# MSE312_SIMRACER.net
KiCad netlist of a schematic drawn in Altium Designer
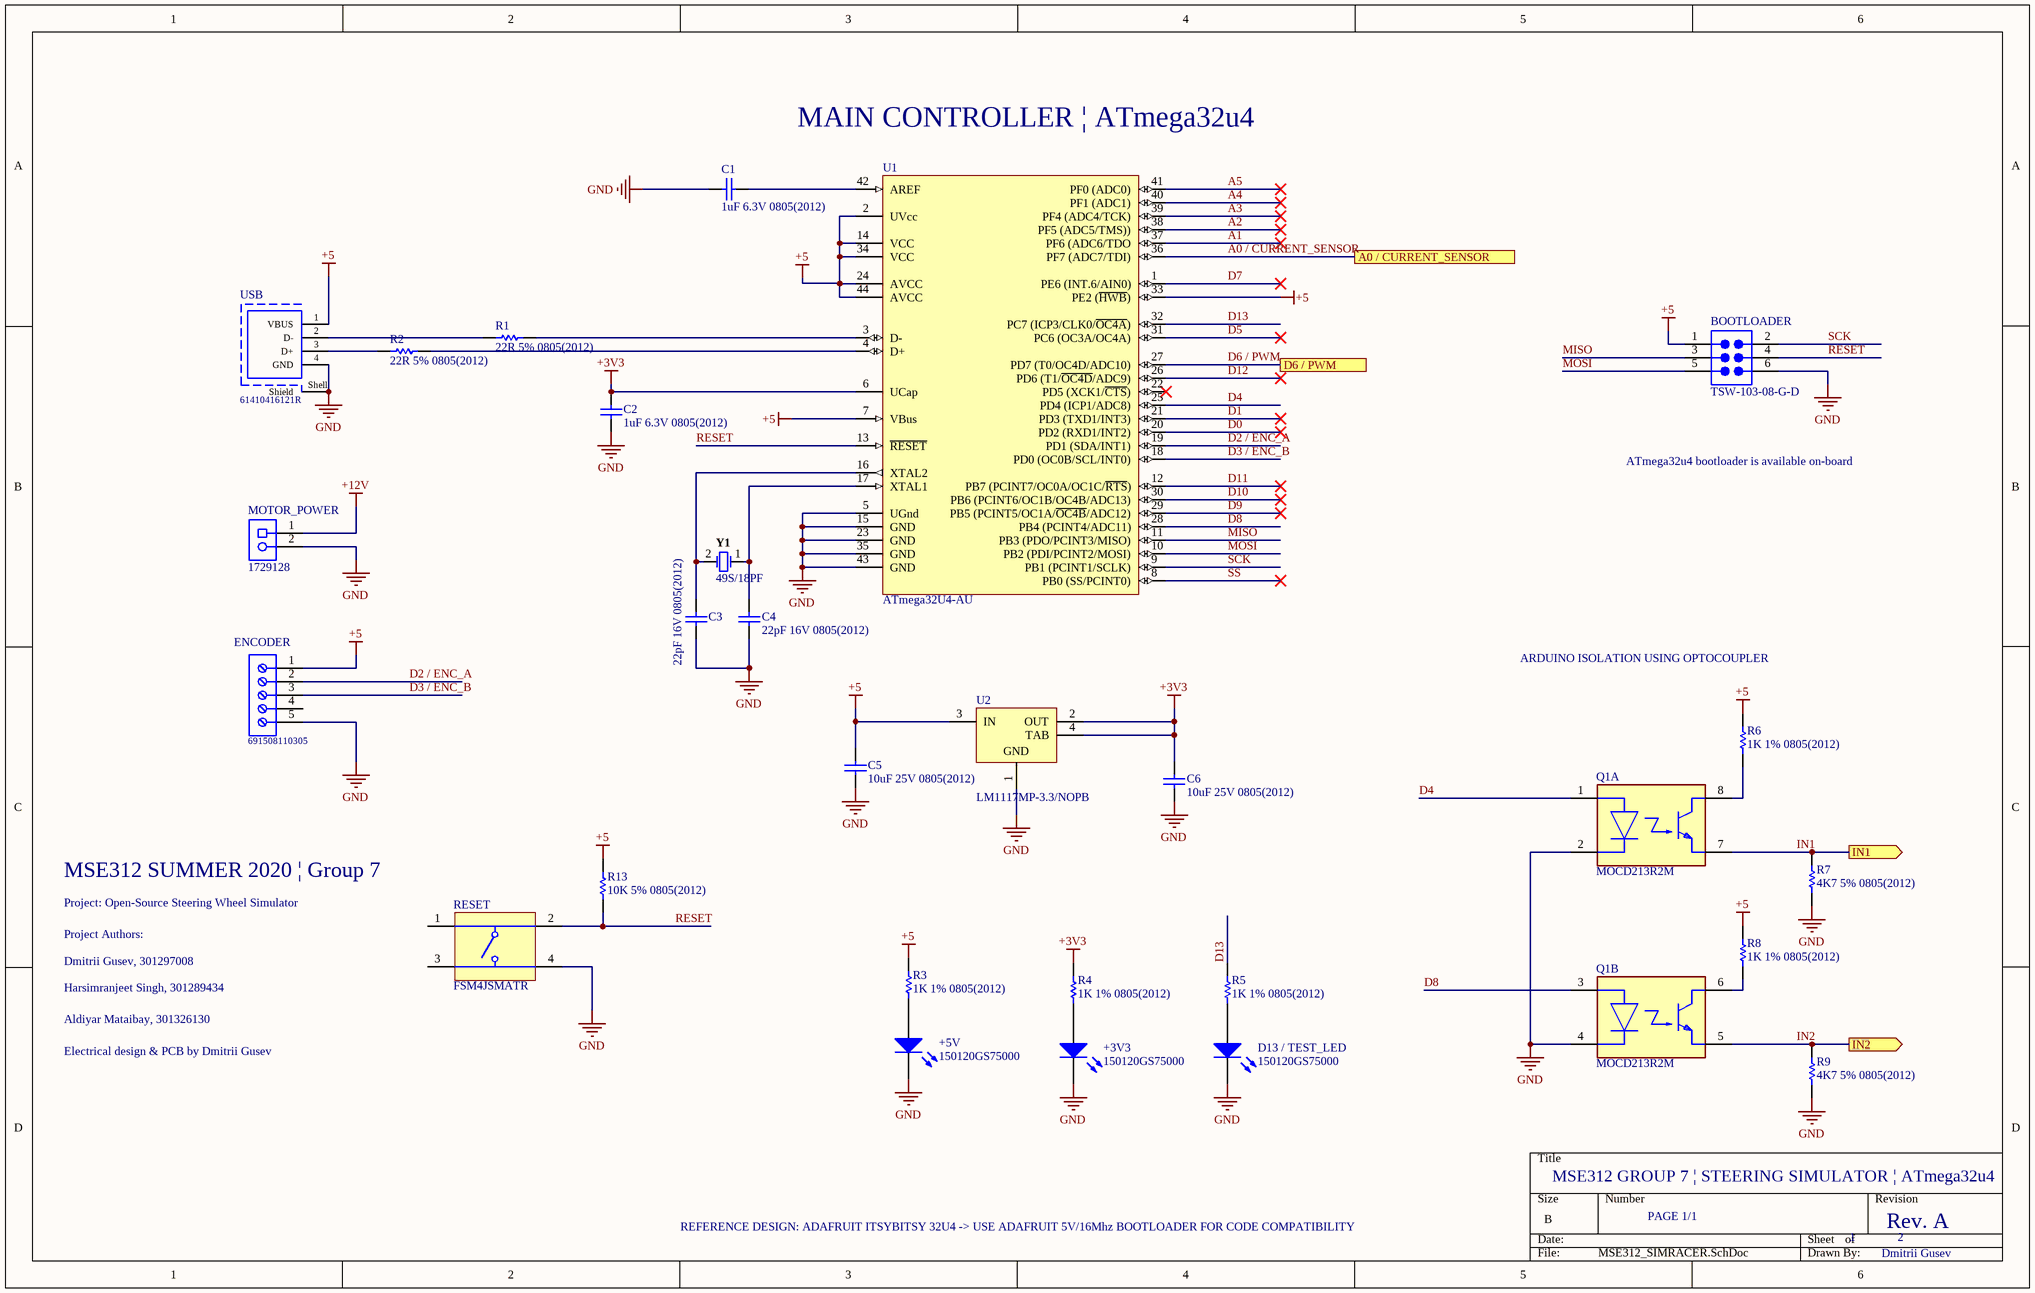
[diagram p0: MSE312_SIMRACER.SchDoc]

(export (version "E")
  (design (tool "Eeschema 10.0.6"))
  (components
    (comp (ref "+3V3")
      (value "150120GS75000")
      (footprint "1206_A")
      (description "SMD mono-color Chip LED, WL-SMCW, Green")
      (fields (field (name "MANUFACTURER") "Wuerth Elektronik"))
      (libsource (lib "Altium Content Vault") (part "WE-LED_K1A2-2"))
    )
    (comp (ref "+5V")
      (value "150120GS75000")
      (footprint "1206_A")
      (description "SMD mono-color Chip LED, WL-SMCW, Green")
      (fields (field (name "MANUFACTURER") "Wuerth Elektronik"))
      (libsource (lib "Altium Content Vault") (part "WE-LED_K1A2-2"))
    )
    (comp (ref "BOOTLOADER")
      (value "TSW-103-08-G-D")
      (footprint "SMTC-TSW-103-08-X-D")
      (fields (field (name "MANUFACTURER") "Samtec"))
      (libsource (lib "Altium Content Vault") (part "SMTC-TSW-103-08-X-D"))
    )
    (comp (ref "C1")
      (value "1uF 6.3V 0805(2012)")
      (footprint "CAPC0805(2012)145_N")
      (description "CAP 1uF 6.3V ±10% 0805 (2012 Metric) Thickness 1.45mm SMD")
      (fields (field (name "TOLERANCE") "Â±10%"))
      (libsource (lib "Altium Content Vault") (part "CAP"))
    )
    (comp (ref "C2")
      (value "1uF 6.3V 0805(2012)")
      (footprint "CAPC0805(2012)145_N")
      (description "CAP 1uF 6.3V ±10% 0805 (2012 Metric) Thickness 1.45mm SMD")
      (fields (field (name "TOLERANCE") "Â±10%"))
      (libsource (lib "Altium Content Vault") (part "CAP"))
    )
    (comp (ref "C3")
      (value "22pF 16V 0805(2012)")
      (footprint "CAPC0805(2012)100_N")
      (description "CAP 22pF 16V ±0.5pF 0805 (2012 Metric) Thickness 1mm SMD")
      (fields (field (name "TOLERANCE") "Â±0.5pF"))
      (libsource (lib "Altium Content Vault") (part "CAP"))
    )
    (comp (ref "C4")
      (value "22pF 16V 0805(2012)")
      (footprint "CAPC0805(2012)100_N")
      (description "CAP 22pF 16V ±0.5pF 0805 (2012 Metric) Thickness 1mm SMD")
      (fields (field (name "TOLERANCE") "Â±0.5pF"))
      (libsource (lib "Altium Content Vault") (part "CAP"))
    )
    (comp (ref "C5")
      (value "10uF 25V 0805(2012)")
      (footprint "CAPC0805(2012)145_N")
      (description "CAP 10uF 25V ±10% 0805 (2012 Metric) Thickness 1.45mm SMD")
      (fields (field (name "TOLERANCE") "Â±10%"))
      (libsource (lib "Altium Content Vault") (part "CAP"))
    )
    (comp (ref "C6")
      (value "10uF 25V 0805(2012)")
      (footprint "CAPC0805(2012)145_N")
      (description "CAP 10uF 25V ±10% 0805 (2012 Metric) Thickness 1.45mm SMD")
      (fields (field (name "TOLERANCE") "Â±10%"))
      (libsource (lib "Altium Content Vault") (part "CAP"))
    )
    (comp (ref "D13 / TEST_LED")
      (value "150120GS75000")
      (footprint "1206_A")
      (description "SMD mono-color Chip LED, WL-SMCW, Green")
      (fields (field (name "MANUFACTURER") "Wuerth Elektronik"))
      (libsource (lib "Altium Content Vault") (part "WE-LED_K1A2-2"))
    )
    (comp (ref "ENCODER")
      (value "691508110305")
      (footprint "691508110305")
      (description "Serie 5081 - 3.50 mm Horizontal Entry SMT with Rising Cage Clamp WR-TBL, 5 pin")
      (fields (field (name "MANUFACTURER") "Wurth Elektronik") (field (name "PUBLISHER") "WurthElektronik"))
      (libsource (lib "Altium Content Vault") (part "WE-CN-1P-F-TB5"))
    )
    (comp (ref "MOTOR_POWER")
      (value "1729128")
      (footprint "PHOE-1729128-2_V")
      (description "PCB Terminal Block, 13.5 A, 400 V, 2-Pin THD, RoHS, Bulk")
      (fields (field (name "MANUFACTURER") "Phoenix Contact"))
      (libsource (lib "Altium Content Vault") (part "CN-2P-F-R2"))
    )
    (comp (ref "Q1")
      (value "MOCD213R2M")
      (footprint "FP-751DZ-MFG")
      (description "OPTOISO 2.5KV 2CH TRANS 8SOIC")
      (fields
        (field (name "MANUFACTURER") "ON Semiconductor")
        (field (name "OCTOPART") "https://octopart.com/mocd213r2m-on+semiconductor-84330505")
      )
      (libsource (lib "Altium Content Vault") (part "5ad21a7a4ea51725ba3cd103b04639f"))
    )
    (comp (ref "R1")
      (value "22R 5% 0805(2012)")
      (footprint "RESC0805(2012)_M")
      (description "22R 0.125W 5% 0805 (2012 Metric)  SMD")
      (fields (field (name "POWER") "0.125 W") (field (name "TOLERANCE") "5 %"))
      (libsource (lib "Altium Content Vault") (part "RES"))
    )
    (comp (ref "R2")
      (value "22R 5% 0805(2012)")
      (footprint "RESC0805(2012)_M")
      (description "22R 0.125W 5% 0805 (2012 Metric)  SMD")
      (fields (field (name "POWER") "0.125 W") (field (name "TOLERANCE") "5 %"))
      (libsource (lib "Altium Content Vault") (part "RES"))
    )
    (comp (ref "R3")
      (value "1K 1% 0805(2012)")
      (footprint "RESC0805(2012)_M")
      (description "1K 0.125W 1% 0805 (2012 Metric)  SMD")
      (fields (field (name "TOLERANCE") "1 %") (field (name "POWER") "0.125 W"))
      (libsource (lib "Altium Content Vault") (part "RES"))
    )
    (comp (ref "R4")
      (value "1K 1% 0805(2012)")
      (footprint "RESC0805(2012)_M")
      (description "1K 0.125W 1% 0805 (2012 Metric)  SMD")
      (fields (field (name "TOLERANCE") "1 %") (field (name "POWER") "0.125 W"))
      (libsource (lib "Altium Content Vault") (part "RES"))
    )
    (comp (ref "R5")
      (value "1K 1% 0805(2012)")
      (footprint "RESC0805(2012)_M")
      (description "1K 0.125W 1% 0805 (2012 Metric)  SMD")
      (fields (field (name "TOLERANCE") "1 %") (field (name "POWER") "0.125 W"))
      (libsource (lib "Altium Content Vault") (part "RES"))
    )
    (comp (ref "R6")
      (value "1K 1% 0805(2012)")
      (footprint "RESC0805(2012)_M")
      (description "1K 0.125W 1% 0805 (2012 Metric)  SMD")
      (fields (field (name "TOLERANCE") "1 %") (field (name "POWER") "0.125 W"))
      (libsource (lib "Altium Content Vault") (part "RES"))
    )
    (comp (ref "R7")
      (value "4K7 5% 0805(2012)")
      (footprint "RESC0805(2012)_N")
      (description "4K7 0.125W 5% 0805 (2012 Metric)  SMD")
      (fields (field (name "POWER") "0.125 W") (field (name "TOLERANCE") "5 %"))
      (libsource (lib "Altium Content Vault") (part "RES"))
    )
    (comp (ref "R8")
      (value "1K 1% 0805(2012)")
      (footprint "RESC0805(2012)_M")
      (description "1K 0.125W 1% 0805 (2012 Metric)  SMD")
      (fields (field (name "TOLERANCE") "1 %") (field (name "POWER") "0.125 W"))
      (libsource (lib "Altium Content Vault") (part "RES"))
    )
    (comp (ref "R9")
      (value "4K7 5% 0805(2012)")
      (footprint "RESC0805(2012)_N")
      (description "4K7 0.125W 5% 0805 (2012 Metric)  SMD")
      (fields (field (name "POWER") "0.125 W") (field (name "TOLERANCE") "5 %"))
      (libsource (lib "Altium Content Vault") (part "RES"))
    )
    (comp (ref "R13")
      (value "10K 5% 0805(2012)")
      (footprint "RESC0805(2012)_L")
      (description "10K 0.125W 5% 0805 (2012 Metric)  SMD")
      (fields (field (name "POWER") "0.125 W") (field (name "TOLERANCE") "5 %"))
      (libsource (lib "Altium Content Vault") (part "RES"))
    )
    (comp (ref "RESET")
      (value "FSM4JSMATR")
      (footprint "TECO-FSM4JSMATR_V")
      (description "Micro Miniature Push Button Switch FSM JSM, 50 mA, -35 to 85 degC, 4-Pin SMD, RoHS, Tape and Reel")
      (fields (field (name "MANUFACTURER") "TE Connectivity"))
      (libsource (lib "Altium Content Vault") (part "SW-SPST-4_A"))
    )
    (comp (ref "U1")
      (value "ATmega32U4-AU")
      (footprint "44ML_M")
      (libsource (lib "Altium Content Vault") (part "MC-8B-ATM16U4-SQ44"))
    )
    (comp (ref "U2")
      (value "LM1117MP-3.3/NOPB")
      (footprint "DCY0004A_L")
      (description "800mA Low-Dropout Linear Regulator, 4-pin SOT-223, Pb-Free")
      (fields (field (name "MANUFACTURER") "Texas Instruments"))
      (libsource (lib "Altium Content Vault") (part "PM-REG-LM1086-SOT4"))
    )
    (comp (ref "USB")
      (value "61410416121R")
      (footprint "61410416121R")
      (description "USB 2.0 Type B Receptacle WR-COM, Horizontal, SMT")
      (fields (field (name "MANUFACTURER") "Wurth Elektronik") (field (name "PUBLISHER") "WurthElektronik"))
      (libsource (lib "Altium Content Vault") (part "WE-USB-4-1SHLD"))
    )
    (comp (ref "Y1")
      (value "49S/18PF")
      (footprint "JPY-49S-18PF")
      (description "Crystal, 16 MHz, 18 pF, -20 to 70 degC, 2-Pin THD")
      (fields (field (name "MANUFACTURER") "Shenzhen Jingpengyuan"))
      (libsource (lib "Altium Content Vault") (part "XTAL-1-2-2"))
    )
  )
  (nets
    (net (code "1") (name "+3V3") (class "Default")
      (node (ref "C2") (pin "2") (pinfunction "2_2") (pintype "passive"))
      (node (ref "C6") (pin "2") (pinfunction "2_2") (pintype "passive"))
      (node (ref "R4") (pin "2") (pinfunction "2_2") (pintype "passive"))
      (node (ref "U1") (pin "6") (pinfunction "UCap_6") (pintype "passive"))
      (node (ref "U2") (pin "2") (pinfunction "OUT_2") (pintype "power_in"))
      (node (ref "U2") (pin "4") (pinfunction "TAB_4") (pintype "power_in"))
    )
    (net (code "2") (name "+5") (class "Default")
      (node (ref "BOOTLOADER") (pin "1") (pinfunction "1_1") (pintype "passive"))
      (node (ref "C5") (pin "2") (pinfunction "2_2") (pintype "passive"))
      (node (ref "ENCODER") (pin "1") (pinfunction "1_1") (pintype "passive"))
      (node (ref "R13") (pin "2") (pinfunction "2_2") (pintype "passive"))
      (node (ref "R3") (pin "2") (pinfunction "2_2") (pintype "passive"))
      (node (ref "R6") (pin "2") (pinfunction "2_2") (pintype "passive"))
      (node (ref "R8") (pin "2") (pinfunction "2_2") (pintype "passive"))
      (node (ref "U1") (pin "14") (pinfunction "VCC_14") (pintype "power_in"))
      (node (ref "U1") (pin "2") (pinfunction "UVcc_2") (pintype "power_in"))
      (node (ref "U1") (pin "24") (pinfunction "AVCC_24") (pintype "power_in"))
      (node (ref "U1") (pin "33") (pinfunction "PE2_(~{HWB})_33") (pintype "bidirectional"))
      (node (ref "U1") (pin "34") (pinfunction "VCC_34") (pintype "power_in"))
      (node (ref "U1") (pin "44") (pinfunction "AVCC_44") (pintype "power_in"))
      (node (ref "U1") (pin "7") (pinfunction "VBus_7") (pintype "input"))
      (node (ref "U2") (pin "3") (pinfunction "IN_3") (pintype "power_in"))
      (node (ref "USB") (pin "1") (pinfunction "VBUS_1") (pintype "passive"))
    )
    (net (code "3") (name "+12V") (class "Default")
      (node (ref "MOTOR_POWER") (pin "1") (pinfunction "1_1") (pintype "passive"))
    )
    (net (code "4") (name "/A0 {slash} CURRENT_SENSOR") (class "Default")
      (node (ref "U1") (pin "36") (pinfunction "PF7_(ADC7/TDI)_36") (pintype "bidirectional"))
    )
    (net (code "5") (name "/A1") (class "Default")
      (node (ref "U1") (pin "37") (pinfunction "PF6_(ADC6/TDO_37") (pintype "bidirectional+no_connect"))
    )
    (net (code "6") (name "/A2") (class "Default")
      (node (ref "U1") (pin "38") (pinfunction "PF5_(ADC5/TMS))_38") (pintype "bidirectional+no_connect"))
    )
    (net (code "7") (name "/A3") (class "Default")
      (node (ref "U1") (pin "39") (pinfunction "PF4_(ADC4/TCK)_39") (pintype "bidirectional+no_connect"))
    )
    (net (code "8") (name "/A4") (class "Default")
      (node (ref "U1") (pin "40") (pinfunction "PF1_(ADC1)_40") (pintype "bidirectional+no_connect"))
    )
    (net (code "9") (name "/A5") (class "Default")
      (node (ref "U1") (pin "41") (pinfunction "PF0_(ADC0)_41") (pintype "bidirectional+no_connect"))
    )
    (net (code "10") (name "/D0") (class "Default")
      (node (ref "U1") (pin "20") (pinfunction "PD2_(RXD1/INT2)_20") (pintype "bidirectional+no_connect"))
    )
    (net (code "11") (name "/D1") (class "Default")
      (node (ref "U1") (pin "21") (pinfunction "PD3_(TXD1/INT3)_21") (pintype "bidirectional+no_connect"))
    )
    (net (code "12") (name "/D2 {slash} ENC_A") (class "Default")
      (node (ref "ENCODER") (pin "2") (pinfunction "2_2") (pintype "passive"))
      (node (ref "U1") (pin "19") (pinfunction "PD1_(SDA/INT1)_19") (pintype "bidirectional"))
    )
    (net (code "13") (name "/D3 {slash} ENC_B") (class "Default")
      (node (ref "ENCODER") (pin "3") (pinfunction "3_3") (pintype "passive"))
      (node (ref "U1") (pin "18") (pinfunction "PD0_(OC0B/SCL/INT0)_18") (pintype "bidirectional"))
    )
    (net (code "14") (name "/D4") (class "Default")
      (node (ref "Q1") (pin "1") (pinfunction "ANODE1_1") (pintype "passive"))
      (node (ref "U1") (pin "25") (pinfunction "PD4_(ICP1/ADC8)_25") (pintype "bidirectional"))
    )
    (net (code "15") (name "/D5") (class "Default")
      (node (ref "U1") (pin "31") (pinfunction "PC6_(OC3A/OC4A)_31") (pintype "bidirectional+no_connect"))
    )
    (net (code "16") (name "/D6 {slash} PWM") (class "Default")
      (node (ref "U1") (pin "27") (pinfunction "PD7_(T0/OC4D/ADC10)_27") (pintype "bidirectional"))
    )
    (net (code "17") (name "/D7") (class "Default")
      (node (ref "U1") (pin "1") (pinfunction "PE6_(INT.6/AIN0)_1") (pintype "bidirectional+no_connect"))
    )
    (net (code "18") (name "/D8") (class "Default")
      (node (ref "Q1") (pin "3") (pinfunction "ANODE2_3") (pintype "passive"))
      (node (ref "U1") (pin "28") (pinfunction "PB4_(PCINT4/ADC11)_28") (pintype "bidirectional"))
    )
    (net (code "19") (name "/D9") (class "Default")
      (node (ref "U1") (pin "29") (pinfunction "PB5_(PCINT5/OC1A/~{OC4B}/ADC12)_29") (pintype "bidirectional+no_connect"))
    )
    (net (code "20") (name "/D10") (class "Default")
      (node (ref "U1") (pin "30") (pinfunction "PB6_(PCINT6/OC1B/OC4B/ADC13)_30") (pintype "bidirectional+no_connect"))
    )
    (net (code "21") (name "/D11") (class "Default")
      (node (ref "U1") (pin "12") (pinfunction "PB7_(PCINT7/OC0A/OC1C/~{RTS})_12") (pintype "bidirectional+no_connect"))
    )
    (net (code "22") (name "/D12") (class "Default")
      (node (ref "U1") (pin "26") (pinfunction "PD6_(T1/~{OC4D}/ADC9)_26") (pintype "bidirectional+no_connect"))
    )
    (net (code "23") (name "/D13") (class "Default")
      (node (ref "R5") (pin "2") (pinfunction "2_2") (pintype "passive"))
      (node (ref "U1") (pin "32") (pinfunction "PC7_(ICP3/CLK0/~{OC4A})_32") (pintype "bidirectional"))
    )
    (net (code "24") (name "/IN1") (class "Default")
      (node (ref "Q1") (pin "7") (pinfunction "EMITTER1_7") (pintype "passive"))
      (node (ref "R7") (pin "2") (pinfunction "2_2") (pintype "passive"))
    )
    (net (code "25") (name "/IN2") (class "Default")
      (node (ref "Q1") (pin "5") (pinfunction "EMITTER2_5") (pintype "passive"))
      (node (ref "R9") (pin "2") (pinfunction "2_2") (pintype "passive"))
    )
    (net (code "26") (name "/MISO") (class "Default")
      (node (ref "BOOTLOADER") (pin "3") (pinfunction "3_3") (pintype "passive"))
      (node (ref "U1") (pin "11") (pinfunction "PB3_(PDO/PCINT3/MISO)_11") (pintype "bidirectional"))
    )
    (net (code "27") (name "/MOSI") (class "Default")
      (node (ref "BOOTLOADER") (pin "5") (pinfunction "5_5") (pintype "passive"))
      (node (ref "U1") (pin "10") (pinfunction "PB2_(PDI/PCINT2/MOSI)_10") (pintype "bidirectional"))
    )
    (net (code "28") (name "/RESET") (class "Default")
      (node (ref "BOOTLOADER") (pin "4") (pinfunction "4_4") (pintype "passive"))
      (node (ref "R13") (pin "1") (pinfunction "1_1") (pintype "passive"))
      (node (ref "RESET") (pin "2") (pinfunction "2_2") (pintype "passive"))
      (node (ref "U1") (pin "13") (pinfunction "~{RESET}_13") (pintype "input"))
    )
    (net (code "29") (name "/SCK") (class "Default")
      (node (ref "BOOTLOADER") (pin "2") (pinfunction "2_2") (pintype "passive"))
      (node (ref "U1") (pin "9") (pinfunction "PB1_(PCINT1/SCLK)_9") (pintype "bidirectional"))
    )
    (net (code "30") (name "/SS") (class "Default")
      (node (ref "U1") (pin "8") (pinfunction "PB0_(SS/PCINT0)_8") (pintype "bidirectional+no_connect"))
    )
    (net (code "31") (name "GND") (class "Default")
      (node (ref "+3V3") (pin "1") (pinfunction "K_1") (pintype "passive"))
      (node (ref "+5V") (pin "1") (pinfunction "K_1") (pintype "passive"))
      (node (ref "BOOTLOADER") (pin "6") (pinfunction "6_6") (pintype "passive"))
      (node (ref "C1") (pin "1") (pinfunction "1_1") (pintype "passive"))
      (node (ref "C2") (pin "1") (pinfunction "1_1") (pintype "passive"))
      (node (ref "C3") (pin "1") (pinfunction "1_1") (pintype "passive"))
      (node (ref "C4") (pin "1") (pinfunction "1_1") (pintype "passive"))
      (node (ref "C5") (pin "1") (pinfunction "1_1") (pintype "passive"))
      (node (ref "C6") (pin "1") (pinfunction "1_1") (pintype "passive"))
      (node (ref "D13 / TEST_LED") (pin "1") (pinfunction "K_1") (pintype "passive"))
      (node (ref "ENCODER") (pin "5") (pinfunction "5_5") (pintype "passive"))
      (node (ref "MOTOR_POWER") (pin "2") (pinfunction "2_2") (pintype "passive"))
      (node (ref "Q1") (pin "2") (pinfunction "CATHODE1_2") (pintype "passive"))
      (node (ref "Q1") (pin "4") (pinfunction "CATHODE2_4") (pintype "passive"))
      (node (ref "R7") (pin "1") (pinfunction "1_1") (pintype "passive"))
      (node (ref "R9") (pin "1") (pinfunction "1_1") (pintype "passive"))
      (node (ref "RESET") (pin "4") (pinfunction "4_4") (pintype "passive"))
      (node (ref "U1") (pin "15") (pinfunction "GND_15") (pintype "power_in"))
      (node (ref "U1") (pin "23") (pinfunction "GND_23") (pintype "power_in"))
      (node (ref "U1") (pin "35") (pinfunction "GND_35") (pintype "power_in"))
      (node (ref "U1") (pin "43") (pinfunction "GND_43") (pintype "power_in"))
      (node (ref "U1") (pin "5") (pinfunction "UGnd_5") (pintype "power_in"))
      (node (ref "U2") (pin "1") (pinfunction "GND_1") (pintype "power_in"))
      (node (ref "USB") (pin "4") (pinfunction "GND_4") (pintype "passive"))
      (node (ref "USB") (pin "Shell") (pinfunction "Shield_Shell") (pintype "passive"))
    )
    (net (code "32") (name "Net-(+3V3-A)") (class "Default")
      (node (ref "+3V3") (pin "2") (pinfunction "A_2") (pintype "passive"))
      (node (ref "R4") (pin "1") (pinfunction "1_1") (pintype "passive"))
    )
    (net (code "33") (name "Net-(+5V-A)") (class "Default")
      (node (ref "+5V") (pin "2") (pinfunction "A_2") (pintype "passive"))
      (node (ref "R3") (pin "1") (pinfunction "1_1") (pintype "passive"))
    )
    (net (code "34") (name "Net-(D13 / TEST_LED-A)") (class "Default")
      (node (ref "D13 / TEST_LED") (pin "2") (pinfunction "A_2") (pintype "passive"))
      (node (ref "R5") (pin "1") (pinfunction "1_1") (pintype "passive"))
    )
    (net (code "35") (name "Net-(Q1A-COLLECTOR1)") (class "Default")
      (node (ref "Q1") (pin "8") (pinfunction "COLLECTOR1_8") (pintype "passive"))
      (node (ref "R6") (pin "1") (pinfunction "1_1") (pintype "passive"))
    )
    (net (code "36") (name "Net-(Q1B-COLLECTOR2)") (class "Default")
      (node (ref "Q1") (pin "6") (pinfunction "COLLECTOR2_6") (pintype "passive"))
      (node (ref "R8") (pin "1") (pinfunction "1_1") (pintype "passive"))
    )
    (net (code "37") (name "Net-(U1-AREF)") (class "Default")
      (node (ref "C1") (pin "2") (pinfunction "2_2") (pintype "passive"))
      (node (ref "U1") (pin "42") (pinfunction "AREF_42") (pintype "input"))
    )
    (net (code "38") (name "Net-(U1-D+)") (class "Default")
      (node (ref "R2") (pin "2") (pinfunction "2_2") (pintype "passive"))
      (node (ref "U1") (pin "4") (pinfunction "D+_4") (pintype "bidirectional"))
    )
    (net (code "39") (name "Net-(U1-D-)") (class "Default")
      (node (ref "R1") (pin "2") (pinfunction "2_2") (pintype "passive"))
      (node (ref "U1") (pin "3") (pinfunction "D-_3") (pintype "bidirectional"))
    )
    (net (code "40") (name "Net-(U1-XTAL1)") (class "Default")
      (node (ref "C4") (pin "2") (pinfunction "2_2") (pintype "passive"))
      (node (ref "U1") (pin "17") (pinfunction "XTAL1_17") (pintype "input"))
      (node (ref "Y1") (pin "1") (pinfunction "1_1") (pintype "passive"))
    )
    (net (code "41") (name "Net-(U1-XTAL2)") (class "Default")
      (node (ref "C3") (pin "2") (pinfunction "2_2") (pintype "passive"))
      (node (ref "U1") (pin "16") (pinfunction "XTAL2_16") (pintype "output"))
      (node (ref "Y1") (pin "2") (pinfunction "2_2") (pintype "passive"))
    )
    (net (code "42") (name "Net-(USB-D+)") (class "Default")
      (node (ref "R2") (pin "1") (pinfunction "1_1") (pintype "passive"))
      (node (ref "USB") (pin "3") (pinfunction "D+_3") (pintype "passive"))
    )
    (net (code "43") (name "Net-(USB-D-)") (class "Default")
      (node (ref "R1") (pin "1") (pinfunction "1_1") (pintype "passive"))
      (node (ref "USB") (pin "2") (pinfunction "D-_2") (pintype "passive"))
    )
    (net (code "44") (name "unconnected-(ENCODER-Pad4)") (class "Default")
      (node (ref "ENCODER") (pin "4") (pinfunction "4_4") (pintype "passive"))
    )
    (net (code "45") (name "unconnected-(RESET-Pad1)") (class "Default")
      (node (ref "RESET") (pin "1") (pinfunction "1_1") (pintype "passive"))
    )
    (net (code "46") (name "unconnected-(RESET-Pad3)") (class "Default")
      (node (ref "RESET") (pin "3") (pinfunction "3_3") (pintype "passive"))
    )
    (net (code "47") (name "unconnected-(U1-PD5_(XCK1{slash}~{CTS})-Pad22)") (class "Default")
      (node (ref "U1") (pin "22") (pinfunction "PD5_(XCK1/~{CTS})_22") (pintype "bidirectional+no_connect"))
    )
  )
)
